# 1_3_3_Power_board_Servos.net
KiCad netlist of a schematic drawn in Altium Designer
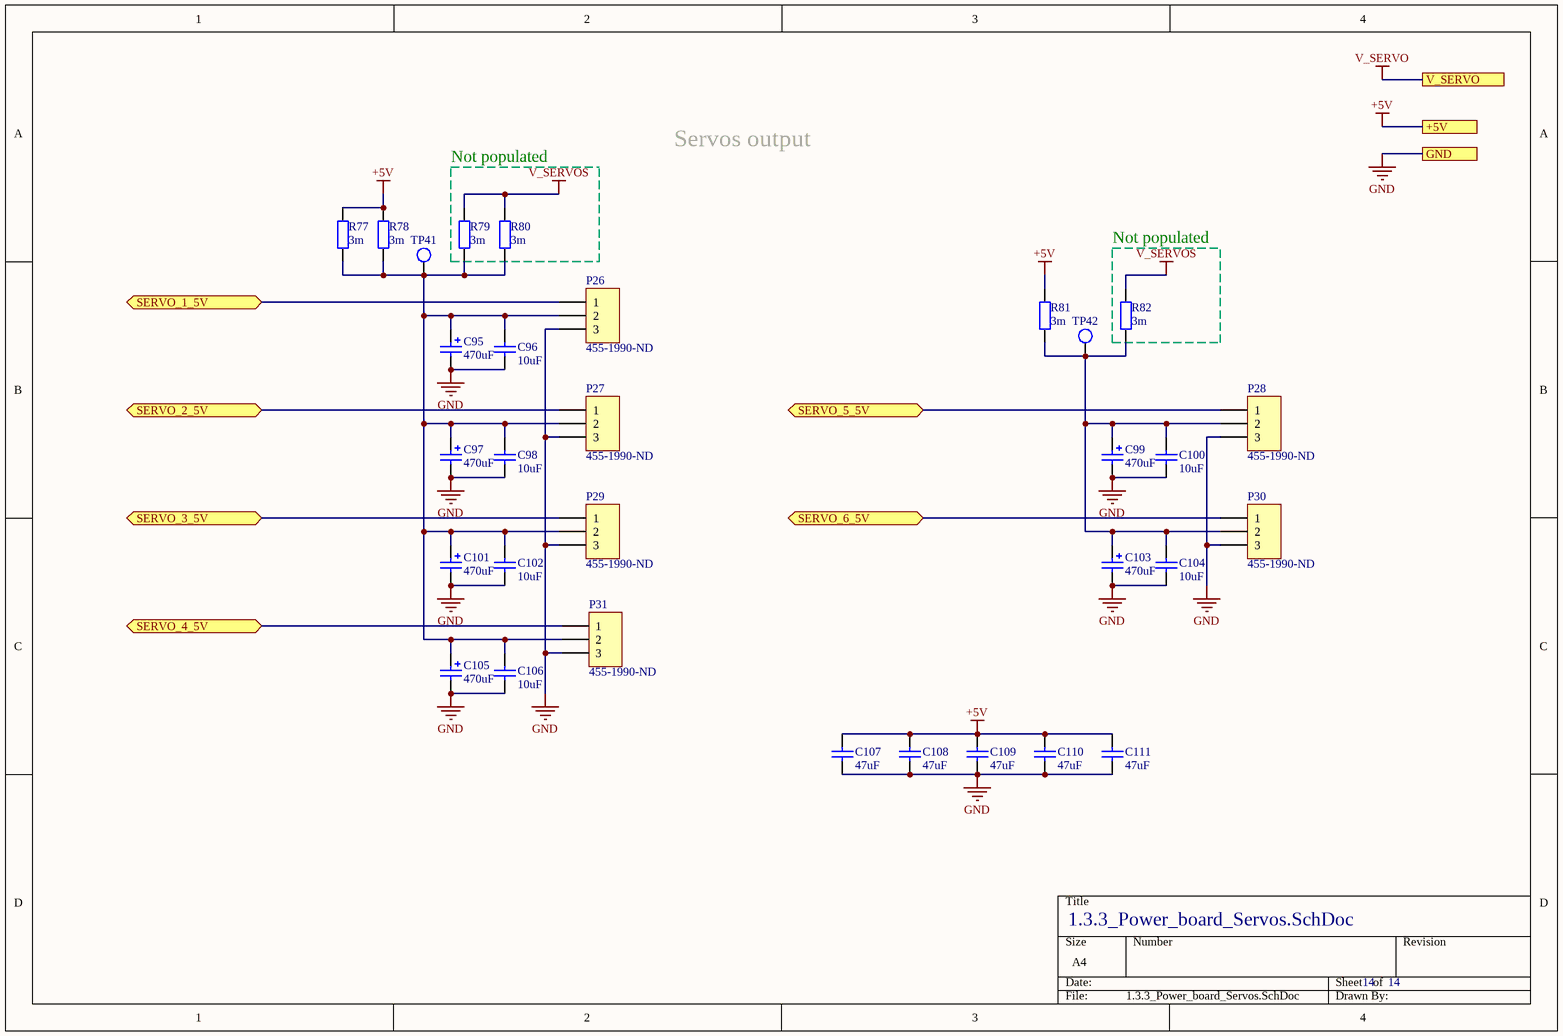
[diagram p0: 1.3.3_Power_board_Servos.SchDoc]

(export (version "E")
  (design (tool "Eeschema 10.0.6"))
  (components
    (comp (ref "C95")
      (value "470uF")
      (footprint "PCV_10x10")
      (description "Polarized Capacitor")
      (libsource (lib "Rocket_library") (part "C_pol_470uF_elec"))
    )
    (comp (ref "C96")
      (value "10uF")
      (footprint "CAP0805W")
      (description "Capacitor")
      (libsource (lib "Rocket_library") (part "C_10uF_16v"))
    )
    (comp (ref "C97")
      (value "470uF")
      (footprint "PCV_10x10")
      (description "Polarized Capacitor")
      (libsource (lib "Rocket_library") (part "C_pol_470uF_elec"))
    )
    (comp (ref "C98")
      (value "10uF")
      (footprint "CAP0805W")
      (description "Capacitor")
      (libsource (lib "Rocket_library") (part "C_10uF_16v"))
    )
    (comp (ref "C99")
      (value "470uF")
      (footprint "PCV_10x10")
      (description "Polarized Capacitor")
      (libsource (lib "Rocket_library") (part "C_pol_470uF_elec"))
    )
    (comp (ref "C100")
      (value "10uF")
      (footprint "CAP0805W")
      (description "Capacitor")
      (libsource (lib "Rocket_library") (part "C_10uF_16v"))
    )
    (comp (ref "C101")
      (value "470uF")
      (footprint "PCV_10x10")
      (description "Polarized Capacitor")
      (libsource (lib "Rocket_library") (part "C_pol_470uF_elec"))
    )
    (comp (ref "C102")
      (value "10uF")
      (footprint "CAP0805W")
      (description "Capacitor")
      (libsource (lib "Rocket_library") (part "C_10uF_16v"))
    )
    (comp (ref "C103")
      (value "470uF")
      (footprint "PCV_10x10")
      (description "Polarized Capacitor")
      (libsource (lib "Rocket_library") (part "C_pol_470uF_elec"))
    )
    (comp (ref "C104")
      (value "10uF")
      (footprint "CAP0805W")
      (description "Capacitor")
      (libsource (lib "Rocket_library") (part "C_10uF_16v"))
    )
    (comp (ref "C105")
      (value "470uF")
      (footprint "PCV_10x10")
      (description "Polarized Capacitor")
      (libsource (lib "Rocket_library") (part "C_pol_470uF_elec"))
    )
    (comp (ref "C106")
      (value "10uF")
      (footprint "CAP0805W")
      (description "Capacitor")
      (libsource (lib "Rocket_library") (part "C_10uF_16v"))
    )
    (comp (ref "C107")
      (value "47uF")
      (footprint "CAP1206W")
      (description "Capacitor")
      (libsource (lib "Rocket_library") (part "C_47uF_25v_1206"))
    )
    (comp (ref "C108")
      (value "47uF")
      (footprint "CAP1206W")
      (description "Capacitor")
      (libsource (lib "Rocket_library") (part "C_47uF_25v_1206"))
    )
    (comp (ref "C109")
      (value "47uF")
      (footprint "CAP1206W")
      (description "Capacitor")
      (libsource (lib "Rocket_library") (part "C_47uF_25v_1206"))
    )
    (comp (ref "C110")
      (value "47uF")
      (footprint "CAP1206W")
      (description "Capacitor")
      (libsource (lib "Rocket_library") (part "C_47uF_25v_1206"))
    )
    (comp (ref "C111")
      (value "47uF")
      (footprint "CAP1206W")
      (description "Capacitor")
      (libsource (lib "Rocket_library") (part "C_47uF_25v_1206"))
    )
    (comp (ref "P26")
      (value "Header 3p JST XA 3A")
      (footprint "CON_JST_XA_ B03B-XASK")
      (fields (field (name "SUPPLIER PART NUMBER 1") "455-1990-ND"))
      (libsource (lib "Rocket_library") (part "Header 3p JST XA 3A"))
    )
    (comp (ref "P27")
      (value "Header 3p JST XA 3A")
      (footprint "CON_JST_XA_ B03B-XASK")
      (fields (field (name "SUPPLIER PART NUMBER 1") "455-1990-ND"))
      (libsource (lib "Rocket_library") (part "Header 3p JST XA 3A"))
    )
    (comp (ref "P28")
      (value "Header 3p JST XA 3A")
      (footprint "CON_JST_XA_ B03B-XASK")
      (fields (field (name "SUPPLIER PART NUMBER 1") "455-1990-ND"))
      (libsource (lib "Rocket_library") (part "Header 3p JST XA 3A"))
    )
    (comp (ref "P29")
      (value "Header 3p JST XA 3A")
      (footprint "CON_JST_XA_ B03B-XASK")
      (fields (field (name "SUPPLIER PART NUMBER 1") "455-1990-ND"))
      (libsource (lib "Rocket_library") (part "Header 3p JST XA 3A"))
    )
    (comp (ref "P30")
      (value "Header 3p JST XA 3A")
      (footprint "CON_JST_XA_ B03B-XASK")
      (fields (field (name "SUPPLIER PART NUMBER 1") "455-1990-ND"))
      (libsource (lib "Rocket_library") (part "Header 3p JST XA 3A"))
    )
    (comp (ref "P31")
      (value "Header 3p JST XA 3A")
      (footprint "CON_JST_XA_ B03B-XASK")
      (fields (field (name "SUPPLIER PART NUMBER 1") "455-1990-ND"))
      (libsource (lib "Rocket_library") (part "Header 3p JST XA 3A"))
    )
    (comp (ref "R77")
      (value "3m")
      (footprint "2010")
      (description "2W 3mOhm")
      (libsource (lib "Rocket_library") (part "R_2010_2W_3mOhm"))
    )
    (comp (ref "R78")
      (value "3m")
      (footprint "2010")
      (description "2W 3mOhm")
      (libsource (lib "Rocket_library") (part "R_2010_2W_3mOhm"))
    )
    (comp (ref "R79")
      (value "3m")
      (footprint "2010")
      (description "2W 3mOhm")
      (libsource (lib "Rocket_library") (part "R_2010_2W_3mOhm"))
    )
    (comp (ref "R80")
      (value "3m")
      (footprint "2010")
      (description "2W 3mOhm")
      (libsource (lib "Rocket_library") (part "R_2010_2W_3mOhm"))
    )
    (comp (ref "R81")
      (value "3m")
      (footprint "2010")
      (description "2W 3mOhm")
      (libsource (lib "Rocket_library") (part "R_2010_2W_3mOhm"))
    )
    (comp (ref "R82")
      (value "3m")
      (footprint "2010")
      (description "2W 3mOhm")
      (libsource (lib "Rocket_library") (part "R_2010_2W_3mOhm"))
    )
    (comp (ref "TP41")
      (value "Test point")
      (footprint "TP")
      (libsource (lib "Rocket_library") (part "Test point"))
    )
    (comp (ref "TP42")
      (value "Test point")
      (footprint "TP")
      (libsource (lib "Rocket_library") (part "Test point"))
    )
  )
  (nets
    (net (code "1") (name "+5V") (class "Default")
      (node (ref "C107") (pin "2") (pinfunction "2_2") (pintype "passive"))
      (node (ref "C108") (pin "2") (pinfunction "2_2") (pintype "passive"))
      (node (ref "C109") (pin "2") (pinfunction "2_2") (pintype "passive"))
      (node (ref "C110") (pin "2") (pinfunction "2_2") (pintype "passive"))
      (node (ref "C111") (pin "2") (pinfunction "2_2") (pintype "passive"))
      (node (ref "R77") (pin "2") (pinfunction "2_2") (pintype "passive"))
      (node (ref "R78") (pin "2") (pinfunction "2_2") (pintype "passive"))
      (node (ref "R81") (pin "2") (pinfunction "2_2") (pintype "passive"))
    )
    (net (code "2") (name "/SERVO_1_5V") (class "Default")
      (node (ref "P26") (pin "1") (pinfunction "1_1") (pintype "passive"))
    )
    (net (code "3") (name "/SERVO_2_5V") (class "Default")
      (node (ref "P27") (pin "1") (pinfunction "1_1") (pintype "passive"))
    )
    (net (code "4") (name "/SERVO_3_5V") (class "Default")
      (node (ref "P29") (pin "1") (pinfunction "1_1") (pintype "passive"))
    )
    (net (code "5") (name "/SERVO_4_5V") (class "Default")
      (node (ref "P31") (pin "1") (pinfunction "1_1") (pintype "passive"))
    )
    (net (code "6") (name "/SERVO_5_5V") (class "Default")
      (node (ref "P28") (pin "1") (pinfunction "1_1") (pintype "passive"))
    )
    (net (code "7") (name "/SERVO_6_5V") (class "Default")
      (node (ref "P30") (pin "1") (pinfunction "1_1") (pintype "passive"))
    )
    (net (code "8") (name "GND") (class "Default")
      (node (ref "C100") (pin "1") (pinfunction "1_1") (pintype "passive"))
      (node (ref "C101") (pin "2") (pinfunction "2_2") (pintype "passive"))
      (node (ref "C102") (pin "1") (pinfunction "1_1") (pintype "passive"))
      (node (ref "C103") (pin "2") (pinfunction "2_2") (pintype "passive"))
      (node (ref "C104") (pin "1") (pinfunction "1_1") (pintype "passive"))
      (node (ref "C105") (pin "2") (pinfunction "2_2") (pintype "passive"))
      (node (ref "C106") (pin "1") (pinfunction "1_1") (pintype "passive"))
      (node (ref "C107") (pin "1") (pinfunction "1_1") (pintype "passive"))
      (node (ref "C108") (pin "1") (pinfunction "1_1") (pintype "passive"))
      (node (ref "C109") (pin "1") (pinfunction "1_1") (pintype "passive"))
      (node (ref "C110") (pin "1") (pinfunction "1_1") (pintype "passive"))
      (node (ref "C111") (pin "1") (pinfunction "1_1") (pintype "passive"))
      (node (ref "C95") (pin "2") (pinfunction "2_2") (pintype "passive"))
      (node (ref "C96") (pin "1") (pinfunction "1_1") (pintype "passive"))
      (node (ref "C97") (pin "2") (pinfunction "2_2") (pintype "passive"))
      (node (ref "C98") (pin "1") (pinfunction "1_1") (pintype "passive"))
      (node (ref "C99") (pin "2") (pinfunction "2_2") (pintype "passive"))
      (node (ref "P26") (pin "3") (pinfunction "3_3") (pintype "passive"))
      (node (ref "P27") (pin "3") (pinfunction "3_3") (pintype "passive"))
      (node (ref "P28") (pin "3") (pinfunction "3_3") (pintype "passive"))
      (node (ref "P29") (pin "3") (pinfunction "3_3") (pintype "passive"))
      (node (ref "P30") (pin "3") (pinfunction "3_3") (pintype "passive"))
      (node (ref "P31") (pin "3") (pinfunction "3_3") (pintype "passive"))
    )
    (net (code "9") (name "Net-(C100-Pad2)") (class "Default")
      (node (ref "C100") (pin "2") (pinfunction "2_2") (pintype "passive"))
      (node (ref "C103") (pin "1") (pinfunction "1_1") (pintype "passive"))
      (node (ref "C104") (pin "2") (pinfunction "2_2") (pintype "passive"))
      (node (ref "C99") (pin "1") (pinfunction "1_1") (pintype "passive"))
      (node (ref "P28") (pin "2") (pinfunction "2_2") (pintype "passive"))
      (node (ref "P30") (pin "2") (pinfunction "2_2") (pintype "passive"))
      (node (ref "R81") (pin "1") (pinfunction "1_1") (pintype "passive"))
      (node (ref "R82") (pin "1") (pinfunction "1_1") (pintype "passive"))
      (node (ref "TP42") (pin "1") (pinfunction "1_1") (pintype "passive"))
    )
    (net (code "10") (name "Net-(C101-Pad1)") (class "Default")
      (node (ref "C101") (pin "1") (pinfunction "1_1") (pintype "passive"))
      (node (ref "C102") (pin "2") (pinfunction "2_2") (pintype "passive"))
      (node (ref "C105") (pin "1") (pinfunction "1_1") (pintype "passive"))
      (node (ref "C106") (pin "2") (pinfunction "2_2") (pintype "passive"))
      (node (ref "C95") (pin "1") (pinfunction "1_1") (pintype "passive"))
      (node (ref "C96") (pin "2") (pinfunction "2_2") (pintype "passive"))
      (node (ref "C97") (pin "1") (pinfunction "1_1") (pintype "passive"))
      (node (ref "C98") (pin "2") (pinfunction "2_2") (pintype "passive"))
      (node (ref "P26") (pin "2") (pinfunction "2_2") (pintype "passive"))
      (node (ref "P27") (pin "2") (pinfunction "2_2") (pintype "passive"))
      (node (ref "P29") (pin "2") (pinfunction "2_2") (pintype "passive"))
      (node (ref "P31") (pin "2") (pinfunction "2_2") (pintype "passive"))
      (node (ref "R77") (pin "1") (pinfunction "1_1") (pintype "passive"))
      (node (ref "R78") (pin "1") (pinfunction "1_1") (pintype "passive"))
      (node (ref "R79") (pin "1") (pinfunction "1_1") (pintype "passive"))
      (node (ref "R80") (pin "1") (pinfunction "1_1") (pintype "passive"))
      (node (ref "TP41") (pin "1") (pinfunction "1_1") (pintype "passive"))
    )
    (net (code "12") (name "V_SERVOS") (class "Default")
      (node (ref "R79") (pin "2") (pinfunction "2_2") (pintype "passive"))
      (node (ref "R80") (pin "2") (pinfunction "2_2") (pintype "passive"))
      (node (ref "R82") (pin "2") (pinfunction "2_2") (pintype "passive"))
    )
  )
)
